# ArduSensor-Button.net
KiCad netlist of a schematic drawn in EAGLE
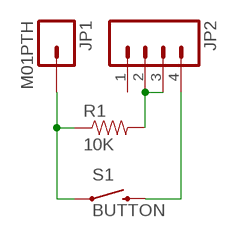
[diagram p0: schematic, sheet 1]

(export (version "E")
  (design (tool "Eeschema 10.0.6"))
  (components
    (comp (ref "JP1")
      (value "M01PTH")
      (footprint "eagle-import:1X01")
      (libsource (lib "eagle-import") (part "M01PTH"))
    )
    (comp (ref "JP2")
      (value "M04PTH")
      (footprint "eagle-import:1X04")
      (libsource (lib "eagle-import") (part "M04PTH"))
    )
    (comp (ref "R1")
      (value "10K")
      (footprint "eagle-import:AXIAL-0.3")
      (libsource (lib "eagle-import") (part "RESISTORAXIAL-0.3"))
    )
    (comp (ref "S1")
      (value "BUTTON")
      (footprint "eagle-import:TACTILE-PTH")
      (libsource (lib "eagle-import") (part "SWITCH-MOMENTARY-2PTH"))
    )
  )
  (nets
    (net (code "1") (name "Net-(R1-1)") (class "Default")
      (node (ref "JP1") (pin "1") (pinfunction "1_1") (pintype "passive"))
      (node (ref "R1") (pin "P$1") (pinfunction "1_P$1") (pintype "passive"))
      (node (ref "S1") (pin "1") (pinfunction "1_1") (pintype "passive"))
    )
    (net (code "2") (name "Net-(R1-2)") (class "Default")
      (node (ref "JP2") (pin "2") (pinfunction "2_2") (pintype "passive"))
      (node (ref "JP2") (pin "3") (pinfunction "3_3") (pintype "passive"))
      (node (ref "R1") (pin "P$2") (pinfunction "2_P$2") (pintype "passive"))
    )
    (net (code "3") (name "Net-(S1-2)") (class "Default")
      (node (ref "JP2") (pin "4") (pinfunction "4_4") (pintype "passive"))
      (node (ref "S1") (pin "3") (pinfunction "2_3") (pintype "passive"))
    )
    (net (code "4") (name "unconnected-(JP2-Pad1)") (class "Default")
      (node (ref "JP2") (pin "1") (pinfunction "1_1") (pintype "passive"))
    )
  )
)
